# sch_sensors.net
KiCad netlist of a schematic drawn in Altium Designer
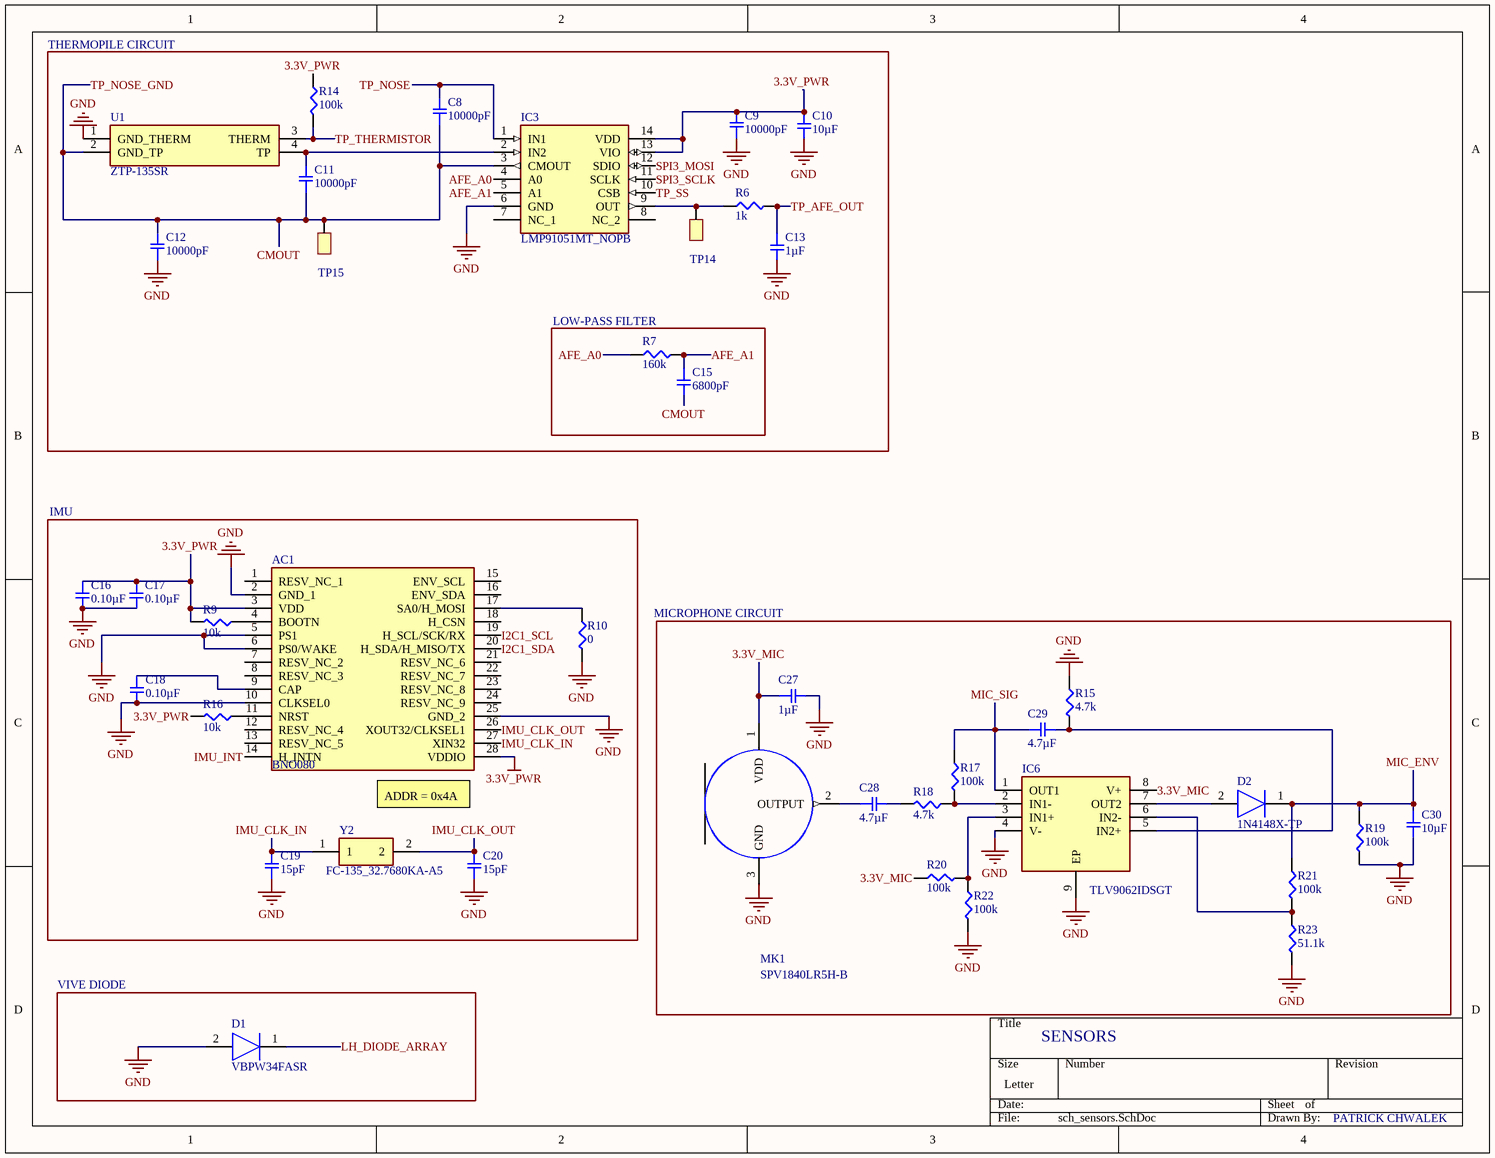
[diagram p0: sch_sensors.SchDoc]

(export (version "E")
  (design (tool "Eeschema 10.0.6"))
  (components
    (comp (ref "AC1")
      (value "BNO080")
      (footprint "SamacSys:BNO080")
      (description "Accelerometer")
      (libsource (lib "*") (part "BNO080"))
    )
    (comp (ref "C8")
      (value "10000pF")
      (footprint "SMD-0402C")
      (description "CAP CER 10000PF 50V X7R 0402")
      (fields
        (field (name "DIGI-KEY PART NUMBER") "490-4762-1-ND")
        (field (name "PART NUMBER") "GCM155R71H103KA55D")
      )
      (libsource (lib "capacitor_murata_0402") (part "GCM155R71H103KA55D"))
    )
    (comp (ref "C9")
      (value "10000pF")
      (footprint "SMD-0402C")
      (description "CAP CER 10000PF 50V X7R 0402")
      (fields
        (field (name "DIGI-KEY PART NUMBER") "490-4762-1-ND")
        (field (name "PART NUMBER") "GCM155R71H103KA55D")
      )
      (libsource (lib "capacitor_murata_0402") (part "GCM155R71H103KA55D"))
    )
    (comp (ref "C10")
      (value "10µF")
      (footprint "SMD-0402C")
      (description "CAP CER 10UF 6.3V X5R 0402")
      (fields
        (field (name "DIGI-KEY PART NUMBER") "490-13211-1-ND")
        (field (name "PART NUMBER") "GRJ155R60J106ME11D")
      )
      (libsource (lib "capacitor_murata_0402") (part "GRJ155R60J106ME11D"))
    )
    (comp (ref "C11")
      (value "10000pF")
      (footprint "SMD-0402C")
      (description "CAP CER 10000PF 50V X7R 0402")
      (fields
        (field (name "DIGI-KEY PART NUMBER") "490-4762-1-ND")
        (field (name "PART NUMBER") "GCM155R71H103KA55D")
      )
      (libsource (lib "capacitor_murata_0402") (part "GCM155R71H103KA55D"))
    )
    (comp (ref "C12")
      (value "10000pF")
      (footprint "SMD-0402C")
      (description "CAP CER 10000PF 50V X7R 0402")
      (fields
        (field (name "DIGI-KEY PART NUMBER") "490-4762-1-ND")
        (field (name "PART NUMBER") "GCM155R71H103KA55D")
      )
      (libsource (lib "capacitor_murata_0402") (part "GCM155R71H103KA55D"))
    )
    (comp (ref "C13")
      (value "1µF")
      (footprint "SMD-0402C")
      (description "CAP CER 1UF 10V X7S 0402")
      (fields
        (field (name "DIGI-KEY PART NUMBER") "490-13409-1-ND")
        (field (name "PART NUMBER") "GCM155C71A105KE38D")
      )
      (libsource (lib "capacitor_murata_0402") (part "GCM155C71A105KE38D"))
    )
    (comp (ref "C15")
      (value "6800pF")
      (footprint "SMD-0402C")
      (description "CAP CER 6800PF 25V X7R 0402")
      (fields
        (field (name "DIGI-KEY PART NUMBER") "490-11422-1-ND")
        (field (name "PART NUMBER") "GRM155R71E682KA01J")
      )
      (libsource (lib "capacitor_murata_0402") (part "GRM155R71E682KA01J"))
    )
    (comp (ref "C16")
      (value "0.10µF")
      (footprint "CAPC1005X55N")
      (description "CAP CER 0.1UF 16V X7R 0402")
      (fields
        (field (name "DIGI-KEY PART NUMBER") "490-4759-1-ND")
        (field (name "PART NUMBER") "GCM155R71C104KA55D")
      )
      (libsource (lib "capacitor_murata_0402") (part "GCM155R71C104KA55D"))
    )
    (comp (ref "C17")
      (value "0.10µF")
      (footprint "CAPC1005X55N")
      (description "CAP CER 0.1UF 16V X7R 0402")
      (fields
        (field (name "DIGI-KEY PART NUMBER") "490-4759-1-ND")
        (field (name "PART NUMBER") "GCM155R71C104KA55D")
      )
      (libsource (lib "capacitor_murata_0402") (part "GCM155R71C104KA55D"))
    )
    (comp (ref "C18")
      (value "0.10µF")
      (footprint "CAPC1005X55N")
      (description "CAP CER 0.1UF 16V X7R 0402")
      (fields
        (field (name "DIGI-KEY PART NUMBER") "490-4759-1-ND")
        (field (name "PART NUMBER") "GCM155R71C104KA55D")
      )
      (libsource (lib "capacitor_murata_0402") (part "GCM155R71C104KA55D"))
    )
    (comp (ref "C19")
      (value "15pF")
      (footprint "CAPC1005X55N")
      (description "CAP CER 15PF 50V NP0 0402")
      (fields
        (field (name "DIGI-KEY PART NUMBER") "490-11147-1-ND")
        (field (name "PART NUMBER") "GCM1555C1H150JA16D")
      )
      (libsource (lib "capacitor_murata_0402") (part "GCM1555C1H150JA16D"))
    )
    (comp (ref "C20")
      (value "15pF")
      (footprint "CAPC1005X55N")
      (description "CAP CER 15PF 50V NP0 0402")
      (fields
        (field (name "DIGI-KEY PART NUMBER") "490-11147-1-ND")
        (field (name "PART NUMBER") "GCM1555C1H150JA16D")
      )
      (libsource (lib "capacitor_murata_0402") (part "GCM1555C1H150JA16D"))
    )
    (comp (ref "C27")
      (value "1µF")
      (footprint "Panasonic_ERJ_0402:SMD-0402-RES")
      (description "CAP CER 1UF 10V X7S 0402")
      (fields
        (field (name "DIGI-KEY PART NUMBER") "490-13409-1-ND")
        (field (name "PART NUMBER") "GCM155C71A105KE38D")
      )
      (libsource (lib "capacitor_murata_0402") (part "GCM155C71A105KE38D"))
    )
    (comp (ref "C28")
      (value "4.7µF")
      (footprint "SMD-0402C")
      (description "CAP CER 4.7UF 4V X5R 0402")
      (fields
        (field (name "DIGI-KEY PART NUMBER") "490-13231-1-ND")
        (field (name "PART NUMBER") "GRM153R60G475ME15D")
      )
      (libsource (lib "capacitor_murata_0402") (part "GRM153R60G475ME15D"))
    )
    (comp (ref "C29")
      (value "4.7µF")
      (footprint "SMD-0402C")
      (description "CAP CER 4.7UF 4V X5R 0402")
      (fields
        (field (name "DIGI-KEY PART NUMBER") "490-13231-1-ND")
        (field (name "PART NUMBER") "GRM153R60G475ME15D")
      )
      (libsource (lib "capacitor_murata_0402") (part "GRM153R60G475ME15D"))
    )
    (comp (ref "C30")
      (value "10µF")
      (footprint "SMD-0402C")
      (description "CAP CER 10UF 6.3V X5R 0402")
      (fields
        (field (name "DIGI-KEY PART NUMBER") "490-13211-1-ND")
        (field (name "PART NUMBER") "GRJ155R60J106ME11D")
      )
      (libsource (lib "capacitor_murata_0402") (part "GRJ155R60J106ME11D"))
    )
    (comp (ref "D1")
      (value "VBPW34FASR")
      (footprint "VBPW34FASR")
      (description "Diode")
      (fields (field (name "MOUSER PART NUMBER") "782-VBPW34FASR") (field (name "RS PART NUMBER") "7689401"))
      (libsource (lib "*") (part "VBPW34FASR"))
    )
    (comp (ref "D2")
      (value "1N4148X-TP")
      (footprint "SamacSys:SODFL1608X70N")
      (description "Diode")
      (fields (field (name "MOUSER PART NUMBER") "833-1N4148X-TP"))
      (libsource (lib "*") (part "1N4148X-TP"))
    )
    (comp (ref "IC3")
      (value "LMP91051MT_NOPB")
      (footprint "SOP65P640X120-14N")
      (description "Integrated Circuit")
      (fields
        (field (name "MANUFACTURER_PART_NUMBER") "LMP91051MT/NOPB")
        (field (name "MOUSER PART NUMBER") "595-LMP91051MT/NOPB")
      )
      (libsource (lib "*") (part "LMP91051MT_NOPB"))
    )
    (comp (ref "IC6")
      (value "TLV9062IDSGT")
      (footprint "SON50P200X200X80-9N")
      (description "Integrated Circuit")
      (fields (field (name "MOUSER PART NUMBER") "595-TLV9062IDSGT"))
      (libsource (lib "SamacSys") (part "TLV9062IDSGT"))
    )
    (comp (ref "MK1")
      (value "SPV1840LR5H-B")
      (footprint "*MIC_SPV1840LR5H-B")
      (description "Mic Mems Analog")
      (fields (field (name "MF") "Knowles"))
      (libsource (lib "schematic_components") (part "SPV1840LR5H-B"))
    )
    (comp (ref "R6")
      (value "1k")
      (footprint "SMD-0402-RES")
      (description "RES SMD 1K OHM 5% 1/10W 0402")
      (fields (field (name "PART NUMBER") "ERJ-2GEJ102X") (field (name "DIGI-KEY PART NUMBER") "P1.0KJCT-ND"))
      (libsource (lib "Panasonic_ERJ_0402") (part "ERJ-2GEJ102X"))
    )
    (comp (ref "R7")
      (value "160k")
      (footprint "SMD-0402-RES")
      (description "RES SMD 160K OHM 5% 1/10W 0402")
      (fields (field (name "PART NUMBER") "ERJ-2GEJ164X") (field (name "DIGI-KEY PART NUMBER") "P160KJCT-ND"))
      (libsource (lib "Panasonic_ERJ_0402") (part "ERJ-2GEJ164X"))
    )
    (comp (ref "R9")
      (value "10k")
      (footprint "SMD-0402-RES")
      (description "RES SMD 10K OHM 5% 1/10W 0402")
      (fields (field (name "PART NUMBER") "ERJ-2GEJ103X") (field (name "DIGI-KEY PART NUMBER") "P10KJCT-ND"))
      (libsource (lib "Panasonic_ERJ_0402") (part "ERJ-2GEJ103X"))
    )
    (comp (ref "R10")
      (value "0")
      (footprint "SMD-0402-RES")
      (description "RES SMD 0K OHM 5% 1/10W 0402")
      (fields (field (name "PART NUMBER") "ERJ-2GEJ103X") (field (name "DIGI-KEY PART NUMBER") "P10KJCT-ND"))
      (libsource (lib "Panasonic_ERJ_0402") (part "ERJ-2GEJ103X"))
    )
    (comp (ref "R14")
      (value "100k")
      (footprint "SMD-0402-RES")
      (description "RES SMD 100K OHM 5% 1/10W 0402")
      (fields (field (name "PART NUMBER") "ERJ-2GEJ103X") (field (name "DIGI-KEY PART NUMBER") "P10KJCT-ND"))
      (libsource (lib "Panasonic_ERJ_0402") (part "ERJ-2GEJ103X"))
    )
    (comp (ref "R15")
      (value "4.7k")
      (footprint "SMD-0402-RES")
      (description "RES SMD 4.7K OHM 5% 1/10W 0402")
      (fields (field (name "PART NUMBER") "ERJ-2GEJ103X") (field (name "DIGI-KEY PART NUMBER") "P10KJCT-ND"))
      (libsource (lib "Panasonic_ERJ_0402") (part "ERJ-2GEJ103X"))
    )
    (comp (ref "R16")
      (value "10k")
      (footprint "SMD-0402-RES")
      (description "RES SMD 10K OHM 5% 1/10W 0402")
      (fields (field (name "PART NUMBER") "ERJ-2GEJ103X") (field (name "DIGI-KEY PART NUMBER") "P10KJCT-ND"))
      (libsource (lib "Panasonic_ERJ_0402") (part "ERJ-2GEJ103X"))
    )
    (comp (ref "R17")
      (value "100k")
      (footprint "SMD-0402-RES")
      (description "RES SMD 100K OHM 5% 1/10W 0402")
      (fields (field (name "PART NUMBER") "ERJ-2GEJ103X") (field (name "DIGI-KEY PART NUMBER") "P10KJCT-ND"))
      (libsource (lib "Panasonic_ERJ_0402") (part "ERJ-2GEJ103X"))
    )
    (comp (ref "R18")
      (value "4.7k")
      (footprint "SMD-0402-RES")
      (description "RES SMD 4.7K OHM 5% 1/10W 0402")
      (fields (field (name "PART NUMBER") "ERJ-2GEJ103X") (field (name "DIGI-KEY PART NUMBER") "P10KJCT-ND"))
      (libsource (lib "Panasonic_ERJ_0402") (part "ERJ-2GEJ103X"))
    )
    (comp (ref "R19")
      (value "100k")
      (footprint "SMD-0402-RES")
      (description "RES SMD 100K OHM 5% 1/10W 0402")
      (fields (field (name "PART NUMBER") "ERJ-2GEJ103X") (field (name "DIGI-KEY PART NUMBER") "P10KJCT-ND"))
      (libsource (lib "Panasonic_ERJ_0402") (part "ERJ-2GEJ103X"))
    )
    (comp (ref "R20")
      (value "100k")
      (footprint "SMD-0402-RES")
      (description "RES SMD 100K OHM 5% 1/10W 0402")
      (fields (field (name "PART NUMBER") "ERJ-2GEJ103X") (field (name "DIGI-KEY PART NUMBER") "P10KJCT-ND"))
      (libsource (lib "Panasonic_ERJ_0402") (part "ERJ-2GEJ103X"))
    )
    (comp (ref "R21")
      (value "100k")
      (footprint "SMD-0402-RES")
      (description "RES SMD 100K OHM 5% 1/10W 0402")
      (fields (field (name "PART NUMBER") "ERJ-2GEJ103X") (field (name "DIGI-KEY PART NUMBER") "P10KJCT-ND"))
      (libsource (lib "Panasonic_ERJ_0402") (part "ERJ-2GEJ103X"))
    )
    (comp (ref "R22")
      (value "100k")
      (footprint "SMD-0402-RES")
      (description "RES SMD 100K OHM 5% 1/10W 0402")
      (fields (field (name "PART NUMBER") "ERJ-2GEJ103X") (field (name "DIGI-KEY PART NUMBER") "P10KJCT-ND"))
      (libsource (lib "Panasonic_ERJ_0402") (part "ERJ-2GEJ103X"))
    )
    (comp (ref "R23")
      (value "51.1k")
      (footprint "SMD-0402-RES")
      (description "RES SMD 51.1K OHM 5% 1/10W 0402")
      (fields (field (name "PART NUMBER") "ERJ-2GEJ103X") (field (name "DIGI-KEY PART NUMBER") "P10KJCT-ND"))
      (libsource (lib "Panasonic_ERJ_0402") (part "ERJ-2GEJ103X"))
    )
    (comp (ref "TP14")
      (value "TestPoint")
      (footprint "TestPoint_0.4mm")
      (libsource (lib "schematic_components") (part "TestPoint"))
    )
    (comp (ref "TP15")
      (value "TestPoint")
      (footprint "TestPoint_0.4mm")
      (libsource (lib "schematic_components") (part "TestPoint"))
    )
    (comp (ref "U1")
      (value "ZTP-135SR")
      (footprint "ZTP-135SR")
      (description "Undefined or Miscellaneous")
      (fields (field (name "MOUSER PART NUMBER") "527-ZTP-135SR"))
      (libsource (lib "SamacSys") (part "ZTP-135SR"))
    )
    (comp (ref "Y2")
      (value "FC-135_32.7680KA-A5")
      (footprint "SamacSys:FC135327680KAAG0")
      (description "Crystal or Oscillator")
      (fields
        (field (name "MANUFACTURER_PART_NUMBER") "FC-135 32.7680KA-A5")
        (field (name "MOUSER PART NUMBER") "732-FC135-32.76KAA3")
      )
      (libsource (lib "*") (part "FC-135_32.7680KA-A3"))
    )
  )
  (nets
    (net (code "1") (name "/3.3V_MIC") (class "Default")
      (node (ref "C27") (pin "1") (pinfunction "1_1") (pintype "passive"))
      (node (ref "IC6") (pin "8") (pinfunction "V+_8") (pintype "passive"))
      (node (ref "MK1") (pin "1") (pinfunction "VDD_1") (pintype "power_in"))
      (node (ref "R20") (pin "1") (pinfunction "1_1") (pintype "passive"))
    )
    (net (code "3") (name "/AFE_A0") (class "Default")
      (node (ref "IC3") (pin "4") (pinfunction "A0_4") (pintype "passive"))
      (node (ref "R7") (pin "1") (pinfunction "1_1") (pintype "passive"))
    )
    (net (code "4") (name "/AFE_A1") (class "Default")
      (node (ref "C15") (pin "1") (pinfunction "1_1") (pintype "passive"))
      (node (ref "IC3") (pin "5") (pinfunction "A1_5") (pintype "passive"))
      (node (ref "R7") (pin "2") (pinfunction "2_2") (pintype "passive"))
    )
    (net (code "5") (name "/CMOUT") (class "Default")
      (node (ref "C11") (pin "1") (pinfunction "1_1") (pintype "passive"))
      (node (ref "C12") (pin "2") (pinfunction "2_2") (pintype "passive"))
      (node (ref "C15") (pin "2") (pinfunction "2_2") (pintype "passive"))
      (node (ref "C8") (pin "1") (pinfunction "1_1") (pintype "passive"))
      (node (ref "IC3") (pin "3") (pinfunction "CMOUT_3") (pintype "output"))
      (node (ref "TP15") (pin "1") (pinfunction "1_1") (pintype "passive"))
      (node (ref "U1") (pin "2") (pinfunction "GND_TP_2") (pintype "passive"))
    )
    (net (code "6") (name "/I2C1_SCL") (class "Default")
      (node (ref "AC1") (pin "19") (pinfunction "H_SCL/SCK/RX_19") (pintype "passive"))
    )
    (net (code "7") (name "/I2C1_SDA") (class "Default")
      (node (ref "AC1") (pin "20") (pinfunction "H_SDA/H_MISO/TX_20") (pintype "passive"))
    )
    (net (code "8") (name "/IMU_CLK_IN") (class "Default")
      (node (ref "AC1") (pin "27") (pinfunction "XIN32_27") (pintype "passive"))
      (node (ref "C19") (pin "1") (pinfunction "1_1") (pintype "passive"))
      (node (ref "Y2") (pin "1") (pinfunction "1_1") (pintype "passive"))
    )
    (net (code "9") (name "/IMU_CLK_OUT") (class "Default")
      (node (ref "AC1") (pin "26") (pinfunction "XOUT32/CLKSEL1_26") (pintype "passive"))
      (node (ref "C20") (pin "1") (pinfunction "1_1") (pintype "passive"))
      (node (ref "Y2") (pin "2") (pinfunction "2_2") (pintype "passive"))
    )
    (net (code "10") (name "/IMU_INT") (class "Default")
      (node (ref "AC1") (pin "14") (pinfunction "H_INTN_14") (pintype "passive"))
    )
    (net (code "11") (name "/LH_DIODE_ARRAY") (class "Default")
      (node (ref "D1") (pin "1") (pinfunction "A_1") (pintype "passive"))
    )
    (net (code "12") (name "/MIC_ENV") (class "Default")
      (node (ref "C30") (pin "1") (pinfunction "1_1") (pintype "passive"))
      (node (ref "D2") (pin "1") (pinfunction "K_1") (pintype "passive"))
      (node (ref "R19") (pin "1") (pinfunction "1_1") (pintype "passive"))
      (node (ref "R21") (pin "1") (pinfunction "1_1") (pintype "passive"))
    )
    (net (code "13") (name "/MIC_SIG") (class "Default")
      (node (ref "C29") (pin "1") (pinfunction "1_1") (pintype "passive"))
      (node (ref "IC6") (pin "1") (pinfunction "OUT1_1") (pintype "passive"))
      (node (ref "R17") (pin "1") (pinfunction "1_1") (pintype "passive"))
    )
    (net (code "14") (name "/SPI3_MOSI") (class "Default")
      (node (ref "IC3") (pin "12") (pinfunction "SDIO_12") (pintype "bidirectional"))
    )
    (net (code "15") (name "/SPI3_SCLK") (class "Default")
      (node (ref "IC3") (pin "11") (pinfunction "SCLK_11") (pintype "input"))
    )
    (net (code "16") (name "/TP_AFE_OUT") (class "Default")
      (node (ref "C13") (pin "1") (pinfunction "1_1") (pintype "passive"))
      (node (ref "R6") (pin "2") (pinfunction "2_2") (pintype "passive"))
    )
    (net (code "17") (name "/TP_NOSE") (class "Default")
      (node (ref "C8") (pin "2") (pinfunction "2_2") (pintype "passive"))
      (node (ref "IC3") (pin "1") (pinfunction "IN1_1") (pintype "input"))
    )
    (net (code "18") (name "/TP_SS") (class "Default")
      (node (ref "IC3") (pin "10") (pinfunction "CSB_10") (pintype "input"))
    )
    (net (code "19") (name "/TP_THERMISTOR") (class "Default")
      (node (ref "R14") (pin "2") (pinfunction "2_2") (pintype "passive"))
      (node (ref "U1") (pin "3") (pinfunction "THERM_3") (pintype "passive"))
    )
    (net (code "20") (name "3.3V_PWR") (class "Default")
      (node (ref "AC1") (pin "28") (pinfunction "VDDIO_28") (pintype "passive"))
      (node (ref "AC1") (pin "3") (pinfunction "VDD_3") (pintype "passive"))
      (node (ref "C10") (pin "1") (pinfunction "1_1") (pintype "passive"))
      (node (ref "C16") (pin "1") (pinfunction "1_1") (pintype "passive"))
      (node (ref "C17") (pin "1") (pinfunction "1_1") (pintype "passive"))
      (node (ref "C9") (pin "2") (pinfunction "2_2") (pintype "passive"))
      (node (ref "IC3") (pin "13") (pinfunction "VIO_13") (pintype "bidirectional"))
      (node (ref "IC3") (pin "14") (pinfunction "VDD_14") (pintype "power_in"))
      (node (ref "R14") (pin "1") (pinfunction "1_1") (pintype "passive"))
      (node (ref "R16") (pin "2") (pinfunction "2_2") (pintype "passive"))
      (node (ref "R9") (pin "2") (pinfunction "2_2") (pintype "passive"))
    )
    (net (code "21") (name "GND") (class "Default")
      (node (ref "AC1") (pin "10") (pinfunction "CLKSEL0_10") (pintype "passive"))
      (node (ref "AC1") (pin "2") (pinfunction "GND_1_2") (pintype "passive"))
      (node (ref "AC1") (pin "25") (pinfunction "GND_2_25") (pintype "passive"))
      (node (ref "AC1") (pin "5") (pinfunction "PS1_5") (pintype "passive"))
      (node (ref "AC1") (pin "6") (pinfunction "PS0/WAKE_6") (pintype "passive"))
      (node (ref "C10") (pin "2") (pinfunction "2_2") (pintype "passive"))
      (node (ref "C12") (pin "1") (pinfunction "1_1") (pintype "passive"))
      (node (ref "C13") (pin "2") (pinfunction "2_2") (pintype "passive"))
      (node (ref "C16") (pin "2") (pinfunction "2_2") (pintype "passive"))
      (node (ref "C17") (pin "2") (pinfunction "2_2") (pintype "passive"))
      (node (ref "C18") (pin "2") (pinfunction "2_2") (pintype "passive"))
      (node (ref "C19") (pin "2") (pinfunction "2_2") (pintype "passive"))
      (node (ref "C20") (pin "2") (pinfunction "2_2") (pintype "passive"))
      (node (ref "C27") (pin "2") (pinfunction "2_2") (pintype "passive"))
      (node (ref "C30") (pin "2") (pinfunction "2_2") (pintype "passive"))
      (node (ref "C9") (pin "1") (pinfunction "1_1") (pintype "passive"))
      (node (ref "D1") (pin "2") (pinfunction "K_2") (pintype "passive"))
      (node (ref "IC3") (pin "6") (pinfunction "GND_6") (pintype "power_in"))
      (node (ref "IC6") (pin "4") (pinfunction "V-_4") (pintype "passive"))
      (node (ref "IC6") (pin "9") (pinfunction "EP_9") (pintype "passive"))
      (node (ref "MK1") (pin "3") (pinfunction "GND_3") (pintype "passive"))
      (node (ref "R10") (pin "2") (pinfunction "2_2") (pintype "passive"))
      (node (ref "R15") (pin "1") (pinfunction "1_1") (pintype "passive"))
      (node (ref "R19") (pin "2") (pinfunction "2_2") (pintype "passive"))
      (node (ref "R22") (pin "2") (pinfunction "2_2") (pintype "passive"))
      (node (ref "R23") (pin "2") (pinfunction "2_2") (pintype "passive"))
      (node (ref "U1") (pin "1") (pinfunction "GND_THERM_1") (pintype "passive"))
    )
    (net (code "22") (name "Net-(AC1-BOOTN)") (class "Default")
      (node (ref "AC1") (pin "4") (pinfunction "BOOTN_4") (pintype "passive"))
      (node (ref "R9") (pin "1") (pinfunction "1_1") (pintype "passive"))
    )
    (net (code "23") (name "Net-(AC1-CAP)") (class "Default")
      (node (ref "AC1") (pin "9") (pinfunction "CAP_9") (pintype "passive"))
      (node (ref "C18") (pin "1") (pinfunction "1_1") (pintype "passive"))
    )
    (net (code "24") (name "Net-(AC1-NRST)") (class "Default")
      (node (ref "AC1") (pin "11") (pinfunction "NRST_11") (pintype "passive"))
      (node (ref "R16") (pin "1") (pinfunction "1_1") (pintype "passive"))
    )
    (net (code "25") (name "Net-(AC1-SA0{slash}H_MOSI)") (class "Default")
      (node (ref "AC1") (pin "17") (pinfunction "SA0/H_MOSI_17") (pintype "passive"))
      (node (ref "R10") (pin "1") (pinfunction "1_1") (pintype "passive"))
    )
    (net (code "26") (name "Net-(C28-Pad2)") (class "Default")
      (node (ref "C28") (pin "2") (pinfunction "2_2") (pintype "passive"))
      (node (ref "R18") (pin "2") (pinfunction "2_2") (pintype "passive"))
    )
    (net (code "27") (name "Net-(D2-A)") (class "Default")
      (node (ref "D2") (pin "2") (pinfunction "A_2") (pintype "passive"))
      (node (ref "IC6") (pin "7") (pinfunction "OUT2_7") (pintype "passive"))
    )
    (net (code "28") (name "Net-(IC3-IN2)") (class "Default")
      (node (ref "C11") (pin "2") (pinfunction "2_2") (pintype "passive"))
      (node (ref "IC3") (pin "2") (pinfunction "IN2_2") (pintype "input"))
      (node (ref "U1") (pin "4") (pinfunction "TP_4") (pintype "passive"))
    )
    (net (code "29") (name "Net-(IC3-OUT)") (class "Default")
      (node (ref "IC3") (pin "9") (pinfunction "OUT_9") (pintype "output"))
      (node (ref "R6") (pin "1") (pinfunction "1_1") (pintype "passive"))
      (node (ref "TP14") (pin "1") (pinfunction "1_1") (pintype "passive"))
    )
    (net (code "30") (name "Net-(IC6-IN1+)") (class "Default")
      (node (ref "IC6") (pin "3") (pinfunction "IN1+_3") (pintype "passive"))
      (node (ref "R20") (pin "2") (pinfunction "2_2") (pintype "passive"))
      (node (ref "R22") (pin "1") (pinfunction "1_1") (pintype "passive"))
    )
    (net (code "31") (name "Net-(IC6-IN1-)") (class "Default")
      (node (ref "IC6") (pin "2") (pinfunction "IN1-_2") (pintype "passive"))
      (node (ref "R17") (pin "2") (pinfunction "2_2") (pintype "passive"))
      (node (ref "R18") (pin "1") (pinfunction "1_1") (pintype "passive"))
    )
    (net (code "32") (name "Net-(IC6-IN2+)") (class "Default")
      (node (ref "C29") (pin "2") (pinfunction "2_2") (pintype "passive"))
      (node (ref "IC6") (pin "5") (pinfunction "IN2+_5") (pintype "passive"))
      (node (ref "R15") (pin "2") (pinfunction "2_2") (pintype "passive"))
    )
    (net (code "33") (name "Net-(IC6-IN2-)") (class "Default")
      (node (ref "IC6") (pin "6") (pinfunction "IN2-_6") (pintype "passive"))
      (node (ref "R21") (pin "2") (pinfunction "2_2") (pintype "passive"))
      (node (ref "R23") (pin "1") (pinfunction "1_1") (pintype "passive"))
    )
    (net (code "34") (name "Net-(MK1-OUTPUT)") (class "Default")
      (node (ref "C28") (pin "1") (pinfunction "1_1") (pintype "passive"))
      (node (ref "MK1") (pin "2") (pinfunction "OUTPUT_2") (pintype "output"))
    )
    (net (code "35") (name "unconnected-(AC1-ENV_SCL-Pad15)") (class "Default")
      (node (ref "AC1") (pin "15") (pinfunction "ENV_SCL_15") (pintype "passive"))
    )
    (net (code "36") (name "unconnected-(AC1-ENV_SDA-Pad16)") (class "Default")
      (node (ref "AC1") (pin "16") (pinfunction "ENV_SDA_16") (pintype "passive"))
    )
    (net (code "37") (name "unconnected-(AC1-H_CSN-Pad18)") (class "Default")
      (node (ref "AC1") (pin "18") (pinfunction "H_CSN_18") (pintype "passive"))
    )
    (net (code "38") (name "unconnected-(AC1-RESV_NC_1-Pad1)") (class "Default")
      (node (ref "AC1") (pin "1") (pinfunction "RESV_NC_1_1") (pintype "passive"))
    )
    (net (code "39") (name "unconnected-(AC1-RESV_NC_2-Pad7)") (class "Default")
      (node (ref "AC1") (pin "7") (pinfunction "RESV_NC_2_7") (pintype "passive"))
    )
    (net (code "40") (name "unconnected-(AC1-RESV_NC_3-Pad8)") (class "Default")
      (node (ref "AC1") (pin "8") (pinfunction "RESV_NC_3_8") (pintype "passive"))
    )
    (net (code "41") (name "unconnected-(AC1-RESV_NC_4-Pad12)") (class "Default")
      (node (ref "AC1") (pin "12") (pinfunction "RESV_NC_4_12") (pintype "passive"))
    )
    (net (code "42") (name "unconnected-(AC1-RESV_NC_5-Pad13)") (class "Default")
      (node (ref "AC1") (pin "13") (pinfunction "RESV_NC_5_13") (pintype "passive"))
    )
    (net (code "43") (name "unconnected-(AC1-RESV_NC_6-Pad21)") (class "Default")
      (node (ref "AC1") (pin "21") (pinfunction "RESV_NC_6_21") (pintype "passive"))
    )
    (net (code "44") (name "unconnected-(AC1-RESV_NC_7-Pad22)") (class "Default")
      (node (ref "AC1") (pin "22") (pinfunction "RESV_NC_7_22") (pintype "passive"))
    )
    (net (code "45") (name "unconnected-(AC1-RESV_NC_8-Pad23)") (class "Default")
      (node (ref "AC1") (pin "23") (pinfunction "RESV_NC_8_23") (pintype "passive"))
    )
    (net (code "46") (name "unconnected-(AC1-RESV_NC_9-Pad24)") (class "Default")
      (node (ref "AC1") (pin "24") (pinfunction "RESV_NC_9_24") (pintype "passive"))
    )
    (net (code "47") (name "unconnected-(IC3-NC_1-Pad7)") (class "Default")
      (node (ref "IC3") (pin "7") (pinfunction "NC_1_7") (pintype "passive"))
    )
    (net (code "48") (name "unconnected-(IC3-NC_2-Pad8)") (class "Default")
      (node (ref "IC3") (pin "8") (pinfunction "NC_2_8") (pintype "passive"))
    )
  )
)
